# diag.net
KiCad netlist of a schematic drawn in EAGLE
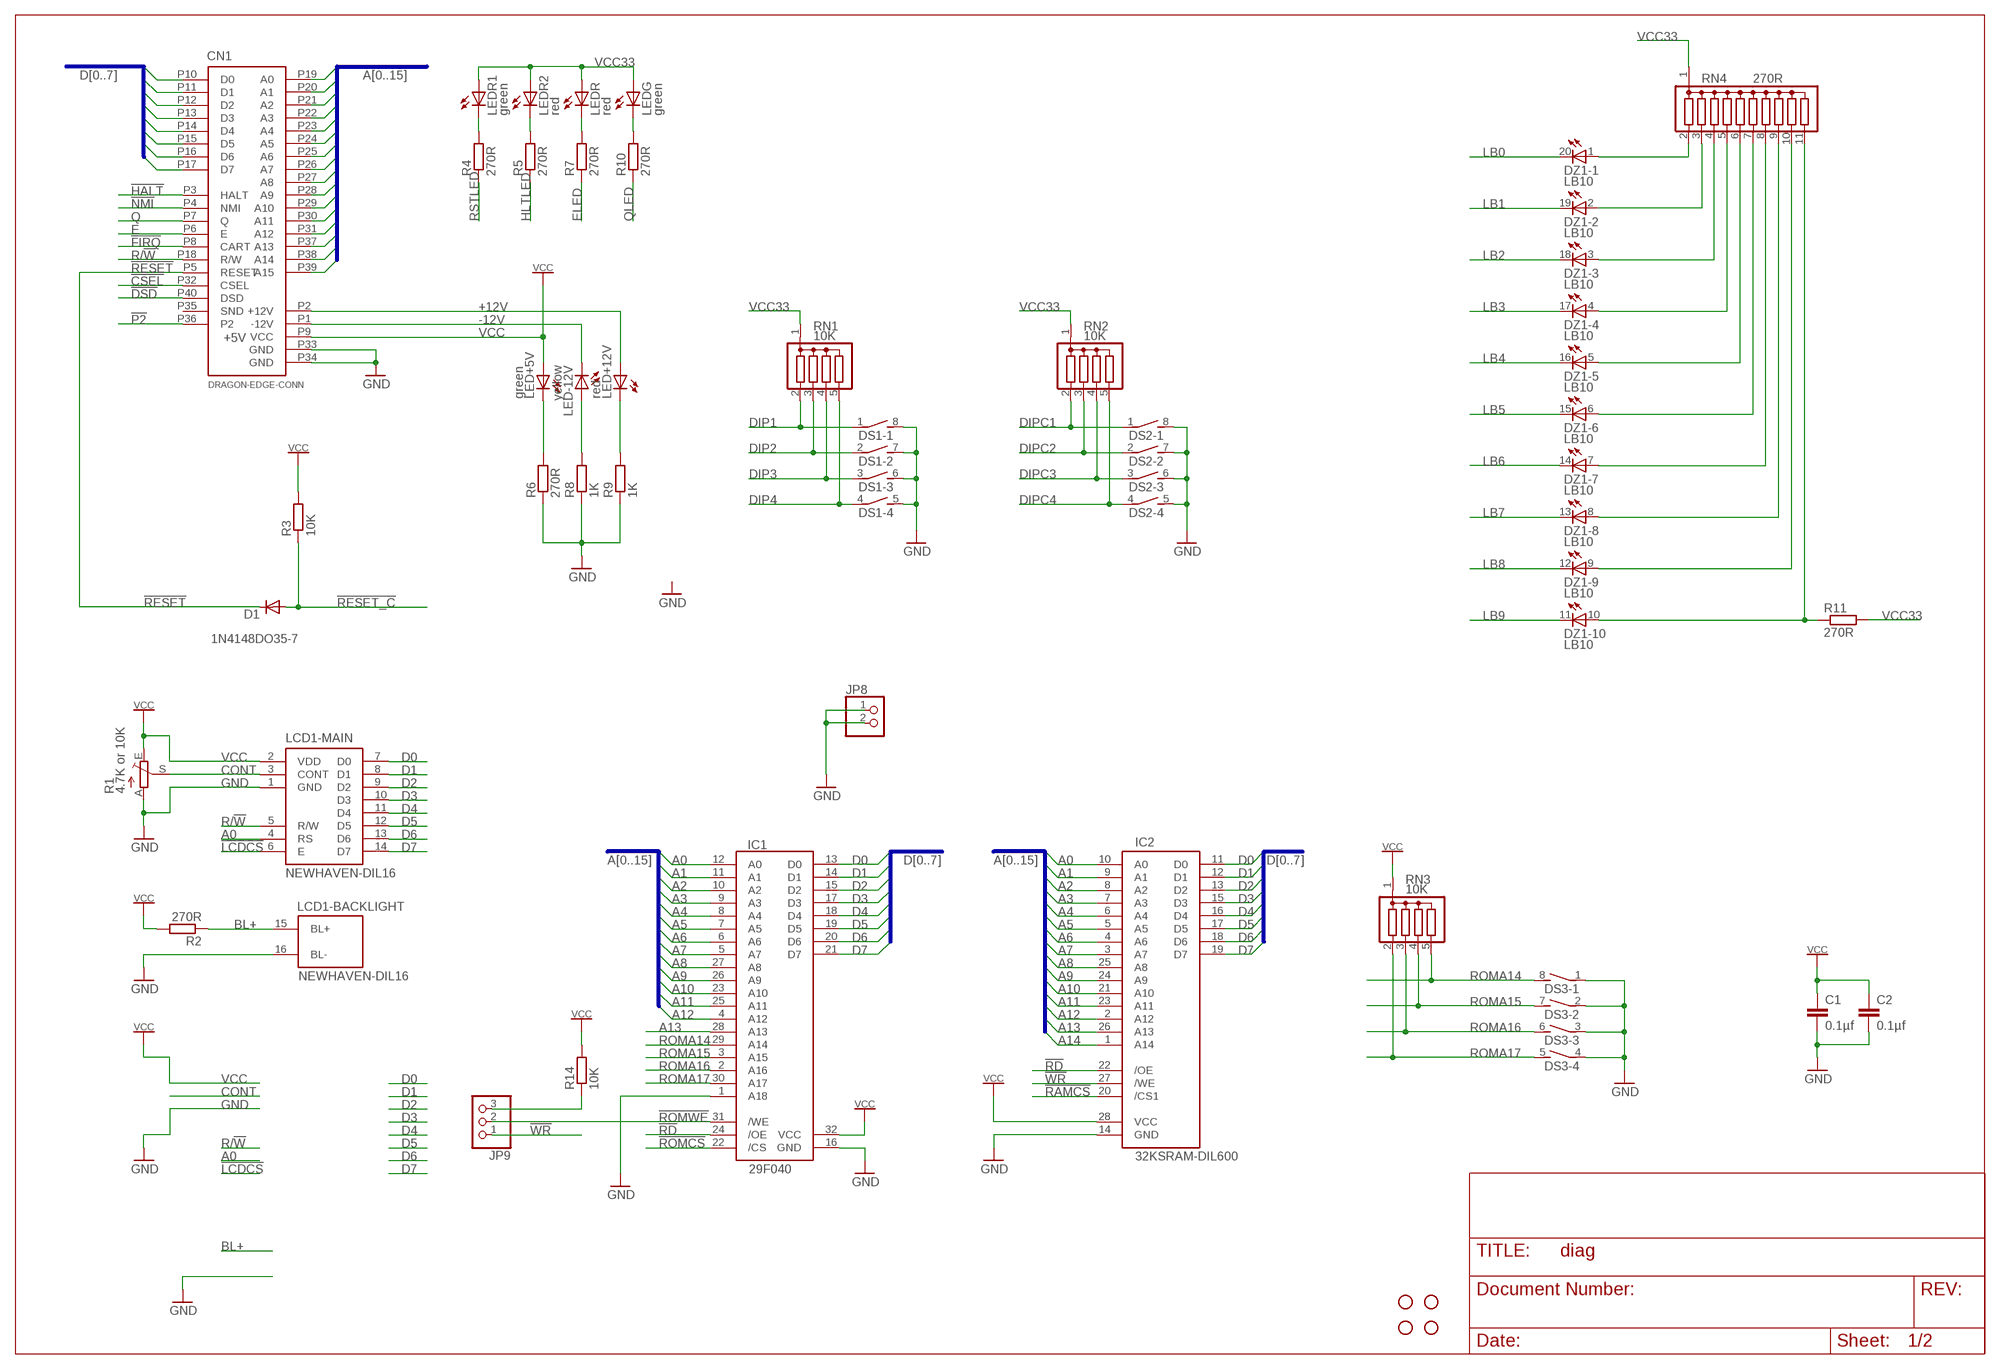
[diagram p0: schematic, sheet 1]
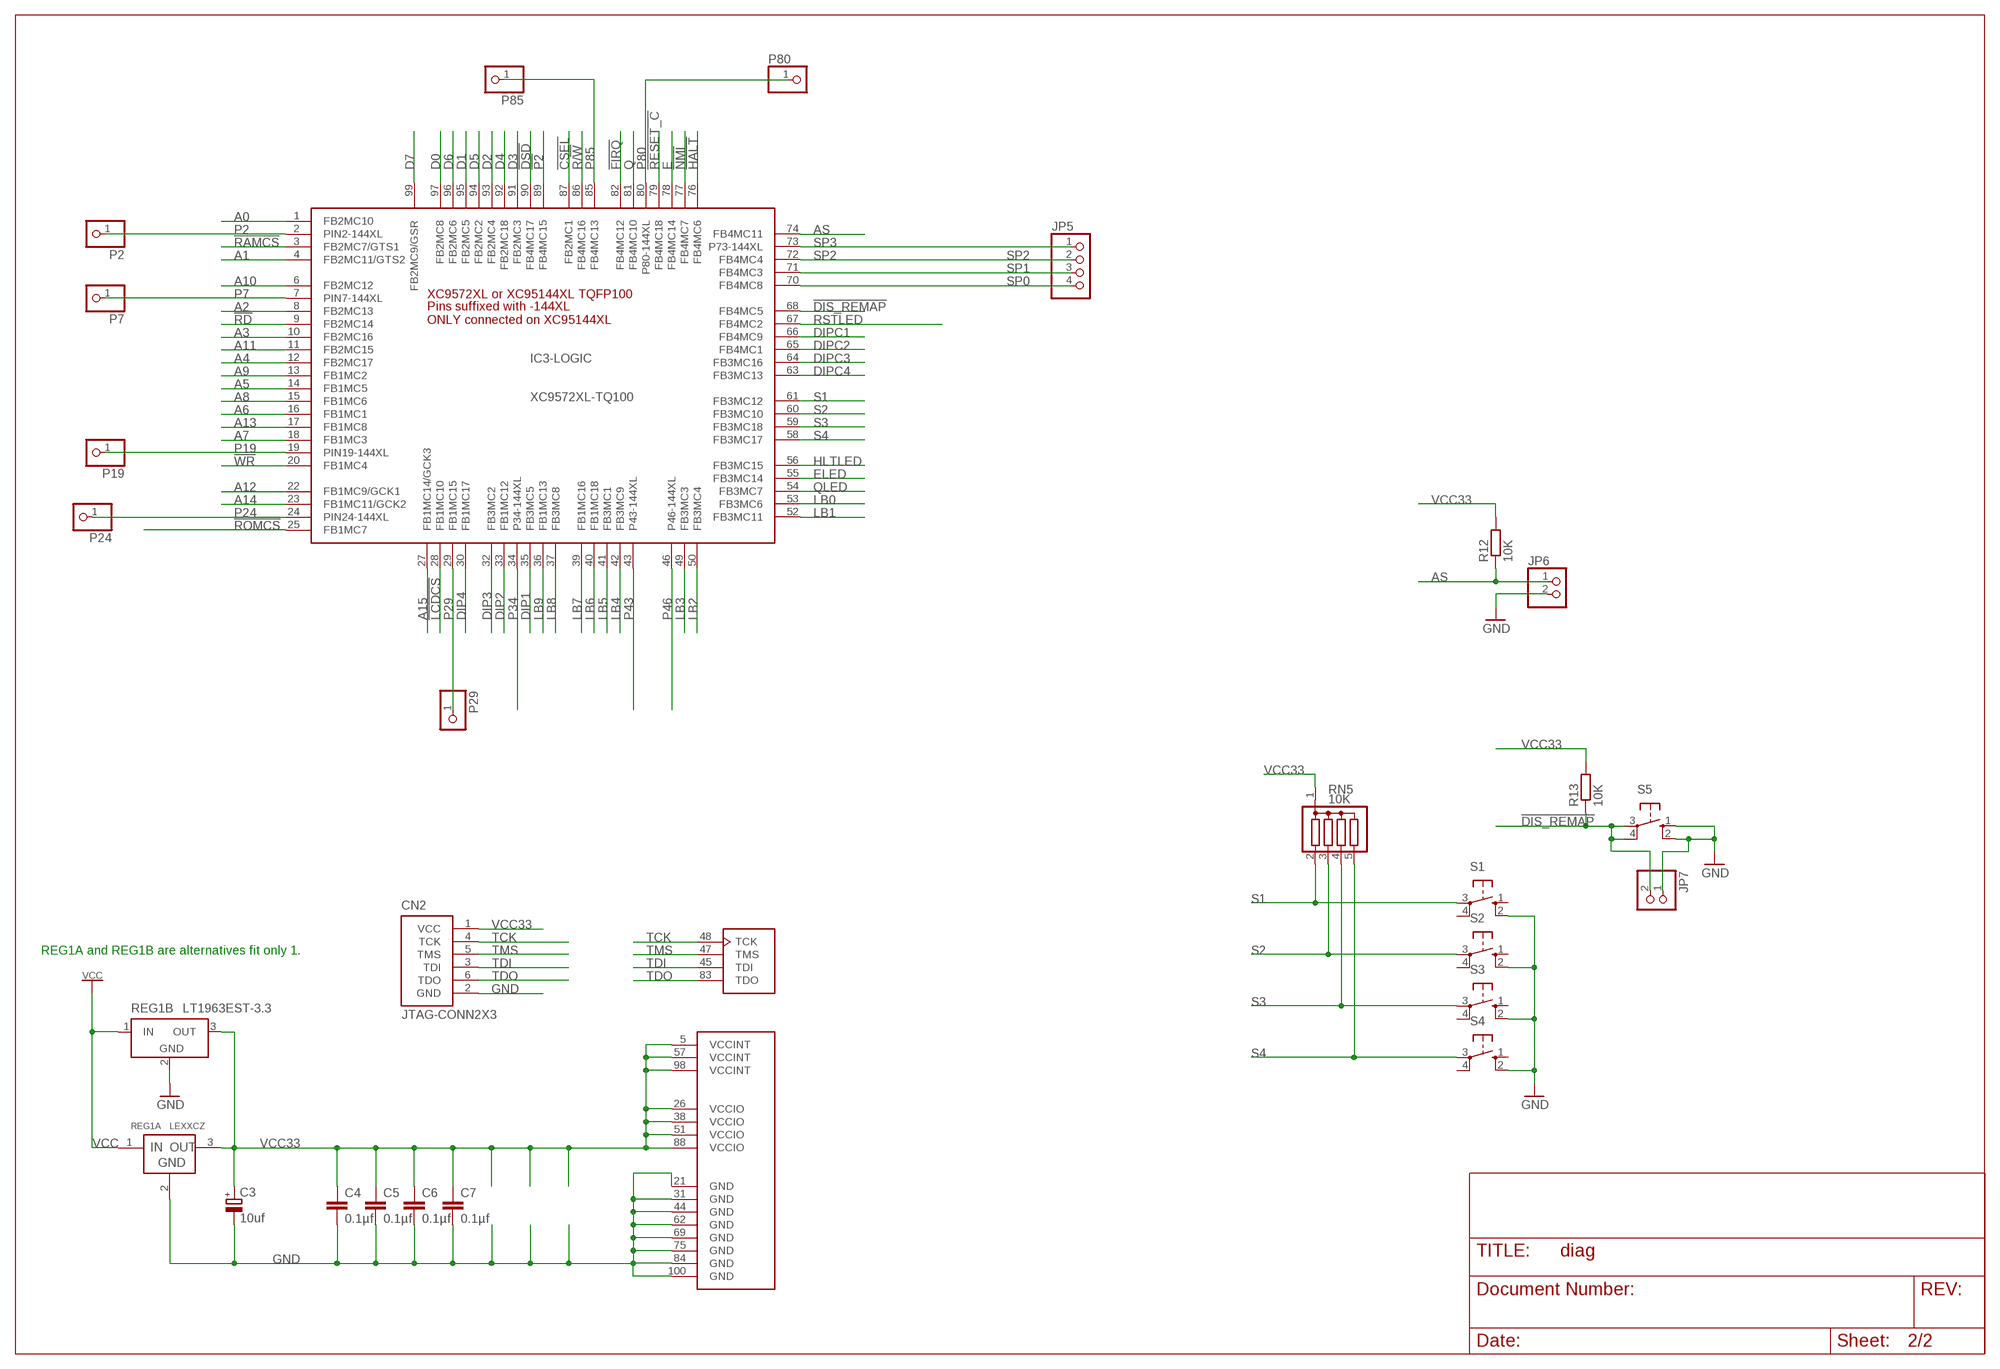
[diagram p1: schematic, sheet 2]

(export (version "E")
  (design (tool "Eeschema 10.0.6"))
  (components
    (comp (ref "C3")
      (value "10uf")
      (footprint "eagle-import:TT2D7")
      (libsource (lib "eagle-import") (part "CPOL-EUTT2D7"))
    )
    (comp (ref "C4")
      (value "0.1µf")
      (footprint "eagle-import:C025-025X050")
      (libsource (lib "eagle-import") (part "C-EU025-025X050"))
    )
    (comp (ref "C5")
      (value "0.1µf")
      (footprint "eagle-import:C025-025X050")
      (libsource (lib "eagle-import") (part "C-EU025-025X050"))
    )
    (comp (ref "C6")
      (value "0.1µf")
      (footprint "eagle-import:C025-025X050")
      (libsource (lib "eagle-import") (part "C-EU025-025X050"))
    )
    (comp (ref "C7")
      (value "0.1µf")
      (footprint "eagle-import:C025-025X050")
      (libsource (lib "eagle-import") (part "C-EU025-025X050"))
    )
    (comp (ref "CN2")
      (value "JTAG-CONN2X3")
      (footprint "eagle-import:2X3")
      (libsource (lib "eagle-import") (part "JTAG-CONN2X3"))
    )
    (comp (ref "IC3")
      (value "XC9572XL-TQ100")
      (footprint "eagle-import:TQ100")
      (libsource (lib "eagle-import") (part "XC9572XL-TQ100"))
    )
    (comp (ref "JP5")
      (value "PINHD-1X4")
      (footprint "eagle-import:1X04")
      (libsource (lib "eagle-import") (part "PINHD-1X4"))
    )
    (comp (ref "JP6")
      (value "PINHD-1X2")
      (footprint "eagle-import:1X02")
      (libsource (lib "eagle-import") (part "PINHD-1X2"))
    )
    (comp (ref "JP7")
      (value "PINHD-1X2")
      (footprint "eagle-import:1X02")
      (libsource (lib "eagle-import") (part "PINHD-1X2"))
    )
    (comp (ref "P2")
      (value "PINHD-1X1")
      (footprint "eagle-import:1X01")
      (libsource (lib "eagle-import") (part "PINHD-1X1"))
    )
    (comp (ref "P7")
      (value "PINHD-1X1")
      (footprint "eagle-import:1X01")
      (libsource (lib "eagle-import") (part "PINHD-1X1"))
    )
    (comp (ref "P19")
      (value "PINHD-1X1")
      (footprint "eagle-import:1X01")
      (libsource (lib "eagle-import") (part "PINHD-1X1"))
    )
    (comp (ref "P24")
      (value "PINHD-1X1")
      (footprint "eagle-import:1X01")
      (libsource (lib "eagle-import") (part "PINHD-1X1"))
    )
    (comp (ref "P29")
      (value "PINHD-1X1")
      (footprint "eagle-import:1X01")
      (libsource (lib "eagle-import") (part "PINHD-1X1"))
    )
    (comp (ref "P80")
      (value "PINHD-1X1")
      (footprint "eagle-import:1X01")
      (libsource (lib "eagle-import") (part "PINHD-1X1"))
    )
    (comp (ref "P85")
      (value "PINHD-1X1")
      (footprint "eagle-import:1X01")
      (libsource (lib "eagle-import") (part "PINHD-1X1"))
    )
    (comp (ref "R12")
      (value "10K")
      (footprint "eagle-import:0207_10")
      (libsource (lib "eagle-import") (part "R-EU_0207/10"))
    )
    (comp (ref "R13")
      (value "10K")
      (footprint "eagle-import:0207_10")
      (libsource (lib "eagle-import") (part "R-EU_0207/10"))
    )
    (comp (ref "REG1A")
      (value "LEXXCZ")
      (footprint "eagle-import:TO92-")
      (libsource (lib "eagle-import") (part "LEXXCZ"))
    )
    (comp (ref "REG1B")
      (value "LT1963EST-3.3")
      (footprint "eagle-import:SOT223")
      (libsource (lib "eagle-import") (part "LT1963EST-3.3"))
    )
    (comp (ref "RN5")
      (value "10K")
      (footprint "eagle-import:SIL5")
      (libsource (lib "eagle-import") (part "G04R"))
    )
    (comp (ref "S1")
      (value "10-XX")
      (footprint "eagle-import:B3F-10XX")
      (fields (field (name "MPN") "B3F-1000"))
      (libsource (lib "eagle-import") (part "10-XX"))
    )
    (comp (ref "S2")
      (value "10-XX")
      (footprint "eagle-import:B3F-10XX")
      (fields (field (name "MPN") "B3F-1000"))
      (libsource (lib "eagle-import") (part "10-XX"))
    )
    (comp (ref "S3")
      (value "10-XX")
      (footprint "eagle-import:B3F-10XX")
      (fields (field (name "MPN") "B3F-1000"))
      (libsource (lib "eagle-import") (part "10-XX"))
    )
    (comp (ref "S4")
      (value "10-XX")
      (footprint "eagle-import:B3F-10XX")
      (fields (field (name "MPN") "B3F-1000"))
      (libsource (lib "eagle-import") (part "10-XX"))
    )
    (comp (ref "S5")
      (value "10-XX")
      (footprint "eagle-import:B3F-10XX")
      (fields (field (name "MPN") "B3F-1000"))
      (libsource (lib "eagle-import") (part "10-XX"))
    )
    (comp (ref "C1")
      (value "0.1µf")
      (footprint "eagle-import:C025-025X050")
      (libsource (lib "eagle-import") (part "C-EU025-025X050"))
    )
    (comp (ref "C2")
      (value "0.1µf")
      (footprint "eagle-import:C025-025X050")
      (libsource (lib "eagle-import") (part "C-EU025-025X050"))
    )
    (comp (ref "CN1")
      (value "DRAGON-EDGE-CONN")
      (footprint "eagle-import:EDGE-40-01")
      (libsource (lib "eagle-import") (part "DRAGON-EDGE-CONN"))
    )
    (comp (ref "D1")
      (value "1N4148DO35-7")
      (footprint "eagle-import:DO35-7")
      (libsource (lib "eagle-import") (part "1N4148DO35-7"))
    )
    (comp (ref "DS1")
      (value "DIP04S")
      (footprint "eagle-import:DIP04S")
      (libsource (lib "eagle-import") (part "DIP04S"))
    )
    (comp (ref "DS2")
      (value "DIP04S")
      (footprint "eagle-import:DIP04S")
      (libsource (lib "eagle-import") (part "DIP04S"))
    )
    (comp (ref "DS3")
      (value "DIP04S")
      (footprint "eagle-import:DIP04S")
      (libsource (lib "eagle-import") (part "DIP04S"))
    )
    (comp (ref "DZ1")
      (value "LB10")
      (footprint "eagle-import:LB10")
      (libsource (lib "eagle-import") (part "LB10"))
    )
    (comp (ref "IC1")
      (value "29F040")
      (footprint "eagle-import:DIL32")
      (libsource (lib "eagle-import") (part "29F040"))
    )
    (comp (ref "IC2")
      (value "32KSRAM-DIL600")
      (footprint "eagle-import:DIL28-6")
      (libsource (lib "eagle-import") (part "32KSRAM-DIL600"))
    )
    (comp (ref "JP1")
      (value "STAND-OFF")
      (footprint "eagle-import:STAND-OFF")
      (libsource (lib "eagle-import") (part "STAND-OFF"))
    )
    (comp (ref "JP2")
      (value "STAND-OFF")
      (footprint "eagle-import:STAND-OFF")
      (libsource (lib "eagle-import") (part "STAND-OFF"))
    )
    (comp (ref "JP3")
      (value "STAND-OFF")
      (footprint "eagle-import:STAND-OFF")
      (libsource (lib "eagle-import") (part "STAND-OFF"))
    )
    (comp (ref "JP4")
      (value "STAND-OFF")
      (footprint "eagle-import:STAND-OFF")
      (libsource (lib "eagle-import") (part "STAND-OFF"))
    )
    (comp (ref "JP8")
      (value "PINHD-1X2")
      (footprint "eagle-import:1X02")
      (libsource (lib "eagle-import") (part "PINHD-1X2"))
    )
    (comp (ref "JP9")
      (value "PINHD-1X3")
      (footprint "eagle-import:1X03")
      (libsource (lib "eagle-import") (part "PINHD-1X3"))
    )
    (comp (ref "LCD1")
      (value "NEWHAVEN-DIL16")
      (footprint "eagle-import:2X08")
      (libsource (lib "eagle-import") (part "NEWHAVEN-DIL16"))
    )
    (comp (ref "LED+5V")
      (value "green")
      (footprint "eagle-import:LED3MM")
      (libsource (lib "eagle-import") (part "LED3MM"))
    )
    (comp (ref "LED+12V")
      (value "red")
      (footprint "eagle-import:LED3MM")
      (libsource (lib "eagle-import") (part "LED3MM"))
    )
    (comp (ref "LED-12V")
      (value "yellow")
      (footprint "eagle-import:LED3MM")
      (libsource (lib "eagle-import") (part "LED3MM"))
    )
    (comp (ref "LEDG")
      (value "green")
      (footprint "eagle-import:LED3MM")
      (libsource (lib "eagle-import") (part "LED3MM"))
    )
    (comp (ref "LEDR")
      (value "red")
      (footprint "eagle-import:LED3MM")
      (libsource (lib "eagle-import") (part "LED3MM"))
    )
    (comp (ref "LEDR1")
      (value "green")
      (footprint "eagle-import:LED3MM")
      (libsource (lib "eagle-import") (part "LED3MM"))
    )
    (comp (ref "LEDR2")
      (value "red")
      (footprint "eagle-import:LED3MM")
      (libsource (lib "eagle-import") (part "LED3MM"))
    )
    (comp (ref "R1")
      (value "4.7K or 10K")
      (footprint "eagle-import:CA9V")
      (libsource (lib "eagle-import") (part "TRIM_EU-CA9V"))
    )
    (comp (ref "R2")
      (value "270R")
      (footprint "eagle-import:0207_10")
      (libsource (lib "eagle-import") (part "R-EU_0207/10"))
    )
    (comp (ref "R3")
      (value "10K")
      (footprint "eagle-import:0204_7")
      (libsource (lib "eagle-import") (part "R-EU_0204/7"))
    )
    (comp (ref "R4")
      (value "270R")
      (footprint "eagle-import:0207_10")
      (libsource (lib "eagle-import") (part "R-EU_0207/10"))
    )
    (comp (ref "R5")
      (value "270R")
      (footprint "eagle-import:0207_10")
      (libsource (lib "eagle-import") (part "R-EU_0207/10"))
    )
    (comp (ref "R6")
      (value "270R")
      (footprint "eagle-import:0207_10")
      (libsource (lib "eagle-import") (part "R-EU_0207/10"))
    )
    (comp (ref "R7")
      (value "270R")
      (footprint "eagle-import:0207_10")
      (libsource (lib "eagle-import") (part "R-EU_0207/10"))
    )
    (comp (ref "R8")
      (value "1K")
      (footprint "eagle-import:0207_10")
      (libsource (lib "eagle-import") (part "R-EU_0207/10"))
    )
    (comp (ref "R9")
      (value "1K")
      (footprint "eagle-import:0207_10")
      (libsource (lib "eagle-import") (part "R-EU_0207/10"))
    )
    (comp (ref "R10")
      (value "270R")
      (footprint "eagle-import:0207_10")
      (libsource (lib "eagle-import") (part "R-EU_0207/10"))
    )
    (comp (ref "R11")
      (value "270R")
      (footprint "eagle-import:0207_10")
      (libsource (lib "eagle-import") (part "R-EU_0207/10"))
    )
    (comp (ref "R14")
      (value "10K")
      (footprint "eagle-import:0207_10")
      (libsource (lib "eagle-import") (part "R-EU_0207/10"))
    )
    (comp (ref "RN1")
      (value "10K")
      (footprint "eagle-import:SIL5")
      (libsource (lib "eagle-import") (part "G04R"))
    )
    (comp (ref "RN2")
      (value "10K")
      (footprint "eagle-import:SIL5")
      (libsource (lib "eagle-import") (part "G04R"))
    )
    (comp (ref "RN3")
      (value "10K")
      (footprint "eagle-import:SIL5")
      (libsource (lib "eagle-import") (part "G04R"))
    )
    (comp (ref "RN4")
      (value "270R")
      (footprint "eagle-import:SIL11")
      (libsource (lib "eagle-import") (part "G10R"))
    )
  )
  (nets
    (net (code "1") (name "+12V") (class "Default")
      (node (ref "CN1") (pin "P2") (pinfunction "+12V_P2") (pintype "passive"))
      (node (ref "LED+12V") (pin "A") (pinfunction "A_A") (pintype "passive"))
    )
    (net (code "2") (name "-12V") (class "Default")
      (node (ref "CN1") (pin "P1") (pinfunction "-12V_P1") (pintype "passive"))
      (node (ref "LED-12V") (pin "K") (pinfunction "C_K") (pintype "passive"))
    )
    (net (code "5") (name "A0") (class "Default")
      (node (ref "CN1") (pin "P19") (pinfunction "A0_P19") (pintype "passive"))
      (node (ref "IC1") (pin "12") (pinfunction "A0_12") (pintype "input"))
      (node (ref "IC2") (pin "10") (pinfunction "A0_10") (pintype "input"))
      (node (ref "IC3") (pin "1") (pinfunction "FB2MC10_1") (pintype "bidirectional"))
      (node (ref "LCD1") (pin "4") (pinfunction "RS_4") (pintype "bidirectional"))
    )
    (net (code "6") (name "A1") (class "Default")
      (node (ref "CN1") (pin "P20") (pinfunction "A1_P20") (pintype "passive"))
      (node (ref "IC1") (pin "11") (pinfunction "A1_11") (pintype "input"))
      (node (ref "IC2") (pin "9") (pinfunction "A1_9") (pintype "input"))
      (node (ref "IC3") (pin "4") (pinfunction "FB2MC11/GTS2_4") (pintype "bidirectional"))
    )
    (net (code "7") (name "A2") (class "Default")
      (node (ref "CN1") (pin "P21") (pinfunction "A2_P21") (pintype "passive"))
      (node (ref "IC1") (pin "10") (pinfunction "A2_10") (pintype "input"))
      (node (ref "IC2") (pin "8") (pinfunction "A2_8") (pintype "input"))
      (node (ref "IC3") (pin "8") (pinfunction "FB2MC13_8") (pintype "bidirectional"))
    )
    (net (code "8") (name "A3") (class "Default")
      (node (ref "CN1") (pin "P22") (pinfunction "A3_P22") (pintype "passive"))
      (node (ref "IC1") (pin "9") (pinfunction "A3_9") (pintype "input"))
      (node (ref "IC2") (pin "7") (pinfunction "A3_7") (pintype "input"))
      (node (ref "IC3") (pin "10") (pinfunction "FB2MC16_10") (pintype "bidirectional"))
    )
    (net (code "9") (name "A4") (class "Default")
      (node (ref "CN1") (pin "P23") (pinfunction "A4_P23") (pintype "passive"))
      (node (ref "IC1") (pin "8") (pinfunction "A4_8") (pintype "input"))
      (node (ref "IC2") (pin "6") (pinfunction "A4_6") (pintype "input"))
      (node (ref "IC3") (pin "12") (pinfunction "FB2MC17_12") (pintype "bidirectional"))
    )
    (net (code "10") (name "A5") (class "Default")
      (node (ref "CN1") (pin "P24") (pinfunction "A5_P24") (pintype "passive"))
      (node (ref "IC1") (pin "7") (pinfunction "A5_7") (pintype "input"))
      (node (ref "IC2") (pin "5") (pinfunction "A5_5") (pintype "input"))
      (node (ref "IC3") (pin "14") (pinfunction "FB1MC5_14") (pintype "bidirectional"))
    )
    (net (code "11") (name "A6") (class "Default")
      (node (ref "CN1") (pin "P25") (pinfunction "A6_P25") (pintype "passive"))
      (node (ref "IC1") (pin "6") (pinfunction "A6_6") (pintype "input"))
      (node (ref "IC2") (pin "4") (pinfunction "A6_4") (pintype "input"))
      (node (ref "IC3") (pin "16") (pinfunction "FB1MC1_16") (pintype "bidirectional"))
    )
    (net (code "12") (name "A7") (class "Default")
      (node (ref "CN1") (pin "P26") (pinfunction "A7_P26") (pintype "passive"))
      (node (ref "IC1") (pin "5") (pinfunction "A7_5") (pintype "input"))
      (node (ref "IC2") (pin "3") (pinfunction "A7_3") (pintype "input"))
      (node (ref "IC3") (pin "18") (pinfunction "FB1MC3_18") (pintype "bidirectional"))
    )
    (net (code "13") (name "A8") (class "Default")
      (node (ref "CN1") (pin "P27") (pinfunction "A8_P27") (pintype "passive"))
      (node (ref "IC1") (pin "27") (pinfunction "A8_27") (pintype "input"))
      (node (ref "IC2") (pin "25") (pinfunction "A8_25") (pintype "input"))
      (node (ref "IC3") (pin "15") (pinfunction "FB1MC6_15") (pintype "bidirectional"))
    )
    (net (code "14") (name "A9") (class "Default")
      (node (ref "CN1") (pin "P28") (pinfunction "A9_P28") (pintype "passive"))
      (node (ref "IC1") (pin "26") (pinfunction "A9_26") (pintype "input"))
      (node (ref "IC2") (pin "24") (pinfunction "A9_24") (pintype "input"))
      (node (ref "IC3") (pin "13") (pinfunction "FB1MC2_13") (pintype "bidirectional"))
    )
    (net (code "15") (name "A10") (class "Default")
      (node (ref "CN1") (pin "P29") (pinfunction "A10_P29") (pintype "passive"))
      (node (ref "IC1") (pin "23") (pinfunction "A10_23") (pintype "input"))
      (node (ref "IC2") (pin "21") (pinfunction "A10_21") (pintype "input"))
      (node (ref "IC3") (pin "6") (pinfunction "FB2MC12_6") (pintype "bidirectional"))
    )
    (net (code "16") (name "A11") (class "Default")
      (node (ref "CN1") (pin "P30") (pinfunction "A11_P30") (pintype "passive"))
      (node (ref "IC1") (pin "25") (pinfunction "A11_25") (pintype "input"))
      (node (ref "IC2") (pin "23") (pinfunction "A11_23") (pintype "input"))
      (node (ref "IC3") (pin "11") (pinfunction "FB2MC15_11") (pintype "bidirectional"))
    )
    (net (code "17") (name "A12") (class "Default")
      (node (ref "CN1") (pin "P31") (pinfunction "A12_P31") (pintype "passive"))
      (node (ref "IC1") (pin "4") (pinfunction "A12_4") (pintype "input"))
      (node (ref "IC2") (pin "2") (pinfunction "A12_2") (pintype "input"))
      (node (ref "IC3") (pin "22") (pinfunction "FB1MC9/GCK1_22") (pintype "bidirectional"))
    )
    (net (code "18") (name "A13") (class "Default")
      (node (ref "CN1") (pin "P37") (pinfunction "A13_P37") (pintype "passive"))
      (node (ref "IC1") (pin "28") (pinfunction "A13_28") (pintype "input"))
      (node (ref "IC2") (pin "26") (pinfunction "A13_26") (pintype "input"))
      (node (ref "IC3") (pin "17") (pinfunction "FB1MC8_17") (pintype "bidirectional"))
    )
    (net (code "19") (name "A14") (class "Default")
      (node (ref "CN1") (pin "P38") (pinfunction "A14_P38") (pintype "passive"))
      (node (ref "IC2") (pin "1") (pinfunction "A14_1") (pintype "input"))
      (node (ref "IC3") (pin "23") (pinfunction "FB1MC11/GCK2_23") (pintype "bidirectional"))
    )
    (net (code "20") (name "A15") (class "Default")
      (node (ref "CN1") (pin "P39") (pinfunction "A15_P39") (pintype "passive"))
      (node (ref "IC3") (pin "27") (pinfunction "FB1MC14/GCK3_27") (pintype "bidirectional"))
    )
    (net (code "21") (name "AS") (class "Default")
      (node (ref "IC3") (pin "74") (pinfunction "FB4MC11_74") (pintype "bidirectional"))
      (node (ref "JP6") (pin "1") (pinfunction "1_1") (pintype "passive"))
      (node (ref "R12") (pin "1") (pinfunction "1_1") (pintype "passive"))
    )
    (net (code "22") (name "BL+") (class "Default")
      (node (ref "LCD1") (pin "15") (pinfunction "BL+_15") (pintype "bidirectional"))
      (node (ref "R2") (pin "1") (pinfunction "1_1") (pintype "passive"))
    )
    (net (code "23") (name "CONT") (class "Default")
      (node (ref "LCD1") (pin "3") (pinfunction "CONT_3") (pintype "bidirectional"))
      (node (ref "R1") (pin "S") (pinfunction "S_S") (pintype "passive"))
    )
    (net (code "24") (name "D0") (class "Default")
      (node (ref "CN1") (pin "P10") (pinfunction "D0_P10") (pintype "passive"))
      (node (ref "IC1") (pin "13") (pinfunction "D0_13") (pintype "bidirectional"))
      (node (ref "IC2") (pin "11") (pinfunction "D0_11") (pintype "bidirectional"))
      (node (ref "IC3") (pin "97") (pinfunction "FB2MC8_97") (pintype "bidirectional"))
      (node (ref "LCD1") (pin "7") (pinfunction "D0_7") (pintype "bidirectional"))
    )
    (net (code "25") (name "D1") (class "Default")
      (node (ref "CN1") (pin "P11") (pinfunction "D1_P11") (pintype "passive"))
      (node (ref "IC1") (pin "14") (pinfunction "D1_14") (pintype "bidirectional"))
      (node (ref "IC2") (pin "12") (pinfunction "D1_12") (pintype "bidirectional"))
      (node (ref "IC3") (pin "95") (pinfunction "FB2MC5_95") (pintype "bidirectional"))
      (node (ref "LCD1") (pin "8") (pinfunction "D1_8") (pintype "bidirectional"))
    )
    (net (code "26") (name "D2") (class "Default")
      (node (ref "CN1") (pin "P12") (pinfunction "D2_P12") (pintype "passive"))
      (node (ref "IC1") (pin "15") (pinfunction "D2_15") (pintype "bidirectional"))
      (node (ref "IC2") (pin "13") (pinfunction "D2_13") (pintype "bidirectional"))
      (node (ref "IC3") (pin "93") (pinfunction "FB2MC4_93") (pintype "bidirectional"))
      (node (ref "LCD1") (pin "9") (pinfunction "D2_9") (pintype "bidirectional"))
    )
    (net (code "27") (name "D3") (class "Default")
      (node (ref "CN1") (pin "P13") (pinfunction "D3_P13") (pintype "passive"))
      (node (ref "IC1") (pin "17") (pinfunction "D3_17") (pintype "bidirectional"))
      (node (ref "IC2") (pin "15") (pinfunction "D3_15") (pintype "bidirectional"))
      (node (ref "IC3") (pin "91") (pinfunction "FB2MC3_91") (pintype "bidirectional"))
      (node (ref "LCD1") (pin "10") (pinfunction "D3_10") (pintype "bidirectional"))
    )
    (net (code "28") (name "D4") (class "Default")
      (node (ref "CN1") (pin "P14") (pinfunction "D4_P14") (pintype "passive"))
      (node (ref "IC1") (pin "18") (pinfunction "D4_18") (pintype "bidirectional"))
      (node (ref "IC2") (pin "16") (pinfunction "D4_16") (pintype "bidirectional"))
      (node (ref "IC3") (pin "92") (pinfunction "FB2MC18_92") (pintype "bidirectional"))
      (node (ref "LCD1") (pin "11") (pinfunction "D4_11") (pintype "bidirectional"))
    )
    (net (code "29") (name "D5") (class "Default")
      (node (ref "CN1") (pin "P15") (pinfunction "D5_P15") (pintype "passive"))
      (node (ref "IC1") (pin "19") (pinfunction "D5_19") (pintype "bidirectional"))
      (node (ref "IC2") (pin "17") (pinfunction "D5_17") (pintype "bidirectional"))
      (node (ref "IC3") (pin "94") (pinfunction "FB2MC2_94") (pintype "bidirectional"))
      (node (ref "LCD1") (pin "12") (pinfunction "D5_12") (pintype "bidirectional"))
    )
    (net (code "30") (name "D6") (class "Default")
      (node (ref "CN1") (pin "P16") (pinfunction "D6_P16") (pintype "passive"))
      (node (ref "IC1") (pin "20") (pinfunction "D6_20") (pintype "bidirectional"))
      (node (ref "IC2") (pin "18") (pinfunction "D6_18") (pintype "bidirectional"))
      (node (ref "IC3") (pin "96") (pinfunction "FB2MC6_96") (pintype "bidirectional"))
      (node (ref "LCD1") (pin "13") (pinfunction "D6_13") (pintype "bidirectional"))
    )
    (net (code "31") (name "D7") (class "Default")
      (node (ref "CN1") (pin "P17") (pinfunction "D7_P17") (pintype "passive"))
      (node (ref "IC1") (pin "21") (pinfunction "D7_21") (pintype "bidirectional"))
      (node (ref "IC2") (pin "19") (pinfunction "D7_19") (pintype "bidirectional"))
      (node (ref "IC3") (pin "99") (pinfunction "FB2MC9/GSR_99") (pintype "bidirectional"))
      (node (ref "LCD1") (pin "14") (pinfunction "D7_14") (pintype "bidirectional"))
    )
    (net (code "32") (name "DIP1") (class "Default")
      (node (ref "DS1") (pin "1") (pinfunction "1_1") (pintype "passive"))
      (node (ref "IC3") (pin "35") (pinfunction "FB3MC5_35") (pintype "bidirectional"))
      (node (ref "RN1") (pin "2") (pinfunction "2_2") (pintype "passive"))
    )
    (net (code "33") (name "DIP2") (class "Default")
      (node (ref "DS1") (pin "2") (pinfunction "1_2") (pintype "passive"))
      (node (ref "IC3") (pin "33") (pinfunction "FB1MC12_33") (pintype "bidirectional"))
      (node (ref "RN1") (pin "3") (pinfunction "3_3") (pintype "passive"))
    )
    (net (code "34") (name "DIP3") (class "Default")
      (node (ref "DS1") (pin "3") (pinfunction "1_3") (pintype "passive"))
      (node (ref "IC3") (pin "32") (pinfunction "FB3MC2_32") (pintype "bidirectional"))
      (node (ref "RN1") (pin "4") (pinfunction "4_4") (pintype "passive"))
    )
    (net (code "35") (name "DIP4") (class "Default")
      (node (ref "DS1") (pin "4") (pinfunction "1_4") (pintype "passive"))
      (node (ref "IC3") (pin "30") (pinfunction "FB1MC17_30") (pintype "bidirectional"))
      (node (ref "RN1") (pin "5") (pinfunction "5_5") (pintype "passive"))
    )
    (net (code "36") (name "DIPC1") (class "Default")
      (node (ref "DS2") (pin "1") (pinfunction "1_1") (pintype "passive"))
      (node (ref "IC3") (pin "66") (pinfunction "FB4MC9_66") (pintype "bidirectional"))
      (node (ref "RN2") (pin "2") (pinfunction "2_2") (pintype "passive"))
    )
    (net (code "37") (name "DIPC2") (class "Default")
      (node (ref "DS2") (pin "2") (pinfunction "1_2") (pintype "passive"))
      (node (ref "IC3") (pin "65") (pinfunction "FB4MC1_65") (pintype "bidirectional"))
      (node (ref "RN2") (pin "3") (pinfunction "3_3") (pintype "passive"))
    )
    (net (code "38") (name "DIPC3") (class "Default")
      (node (ref "DS2") (pin "3") (pinfunction "1_3") (pintype "passive"))
      (node (ref "IC3") (pin "64") (pinfunction "FB3MC16_64") (pintype "bidirectional"))
      (node (ref "RN2") (pin "4") (pinfunction "4_4") (pintype "passive"))
    )
    (net (code "39") (name "DIPC4") (class "Default")
      (node (ref "DS2") (pin "4") (pinfunction "1_4") (pintype "passive"))
      (node (ref "IC3") (pin "63") (pinfunction "FB3MC13_63") (pintype "bidirectional"))
      (node (ref "RN2") (pin "5") (pinfunction "5_5") (pintype "passive"))
    )
    (net (code "40") (name "E") (class "Default")
      (node (ref "CN1") (pin "P6") (pinfunction "E_P6") (pintype "passive"))
      (node (ref "IC3") (pin "78") (pinfunction "FB4MC14_78") (pintype "bidirectional"))
    )
    (net (code "41") (name "ELED") (class "Default")
      (node (ref "IC3") (pin "55") (pinfunction "FB3MC14_55") (pintype "bidirectional"))
      (node (ref "R7") (pin "1") (pinfunction "1_1") (pintype "passive"))
    )
    (net (code "42") (name "GND") (class "Default")
      (node (ref "C1") (pin "2") (pinfunction "2_2") (pintype "passive"))
      (node (ref "C2") (pin "2") (pinfunction "2_2") (pintype "passive"))
      (node (ref "C3") (pin "-") (pinfunction "-_-") (pintype "passive"))
      (node (ref "C4") (pin "2") (pinfunction "2_2") (pintype "passive"))
      (node (ref "C5") (pin "2") (pinfunction "2_2") (pintype "passive"))
      (node (ref "C6") (pin "2") (pinfunction "2_2") (pintype "passive"))
      (node (ref "C7") (pin "2") (pinfunction "2_2") (pintype "passive"))
      (node (ref "CN1") (pin "P33") (pinfunction "GND_P33") (pintype "passive"))
      (node (ref "CN1") (pin "P34") (pinfunction "GND_P34") (pintype "passive"))
      (node (ref "CN2") (pin "2") (pinfunction "GND_2") (pintype "bidirectional"))
      (node (ref "DS1") (pin "5") (pinfunction "2_5") (pintype "passive"))
      (node (ref "DS1") (pin "6") (pinfunction "2_6") (pintype "passive"))
      (node (ref "DS1") (pin "7") (pinfunction "2_7") (pintype "passive"))
      (node (ref "DS1") (pin "8") (pinfunction "2_8") (pintype "passive"))
      (node (ref "DS2") (pin "5") (pinfunction "2_5") (pintype "passive"))
      (node (ref "DS2") (pin "6") (pinfunction "2_6") (pintype "passive"))
      (node (ref "DS2") (pin "7") (pinfunction "2_7") (pintype "passive"))
      (node (ref "DS2") (pin "8") (pinfunction "2_8") (pintype "passive"))
      (node (ref "DS3") (pin "1") (pinfunction "1_1") (pintype "passive"))
      (node (ref "DS3") (pin "2") (pinfunction "1_2") (pintype "passive"))
      (node (ref "DS3") (pin "3") (pinfunction "1_3") (pintype "passive"))
      (node (ref "DS3") (pin "4") (pinfunction "1_4") (pintype "passive"))
      (node (ref "IC1") (pin "1") (pinfunction "A18_1") (pintype "input"))
      (node (ref "IC1") (pin "16") (pinfunction "GND_16") (pintype "power_in"))
      (node (ref "IC2") (pin "14") (pinfunction "GND_14") (pintype "power_in"))
      (node (ref "IC3") (pin "100") (pinfunction "GND_100") (pintype "power_in"))
      (node (ref "IC3") (pin "21") (pinfunction "GND_21") (pintype "power_in"))
      (node (ref "IC3") (pin "31") (pinfunction "GND_31") (pintype "power_in"))
      (node (ref "IC3") (pin "44") (pinfunction "GND_44") (pintype "power_in"))
      (node (ref "IC3") (pin "62") (pinfunction "GND_62") (pintype "power_in"))
      (node (ref "IC3") (pin "69") (pinfunction "GND_69") (pintype "power_in"))
      (node (ref "IC3") (pin "75") (pinfunction "GND_75") (pintype "power_in"))
      (node (ref "IC3") (pin "84") (pinfunction "GND_84") (pintype "power_in"))
      (node (ref "JP6") (pin "2") (pinfunction "2_2") (pintype "passive"))
      (node (ref "JP7") (pin "1") (pinfunction "1_1") (pintype "passive"))
      (node (ref "JP8") (pin "1") (pinfunction "1_1") (pintype "passive"))
      (node (ref "JP8") (pin "2") (pinfunction "2_2") (pintype "passive"))
      (node (ref "LCD1") (pin "1") (pinfunction "GND_1") (pintype "bidirectional"))
      (node (ref "LCD1") (pin "16") (pinfunction "BL-_16") (pintype "bidirectional"))
      (node (ref "R1") (pin "A") (pinfunction "A_A") (pintype "passive"))
      (node (ref "R6") (pin "1") (pinfunction "1_1") (pintype "passive"))
      (node (ref "R8") (pin "1") (pinfunction "1_1") (pintype "passive"))
      (node (ref "R9") (pin "1") (pinfunction "1_1") (pintype "passive"))
      (node (ref "REG1A") (pin "2") (pinfunction "GND_2") (pintype "power_in"))
      (node (ref "REG1B") (pin "2") (pinfunction "GND_2") (pintype "power_in"))
      (node (ref "S1") (pin "2") (pinfunction "S1_2") (pintype "passive"))
      (node (ref "S2") (pin "2") (pinfunction "S1_2") (pintype "passive"))
      (node (ref "S3") (pin "2") (pinfunction "S1_2") (pintype "passive"))
      (node (ref "S4") (pin "2") (pinfunction "S1_2") (pintype "passive"))
      (node (ref "S5") (pin "1") (pinfunction "S_1") (pintype "passive"))
      (node (ref "S5") (pin "2") (pinfunction "S1_2") (pintype "passive"))
    )
    (net (code "43") (name "HLTLED") (class "Default")
      (node (ref "IC3") (pin "56") (pinfunction "FB3MC15_56") (pintype "bidirectional"))
      (node (ref "R5") (pin "1") (pinfunction "1_1") (pintype "passive"))
    )
    (net (code "44") (name "LB0") (class "Default")
      (node (ref "DZ1") (pin "20") (pinfunction "C_20") (pintype "passive"))
      (node (ref "IC3") (pin "53") (pinfunction "FB3MC6_53") (pintype "bidirectional"))
    )
    (net (code "45") (name "LB1") (class "Default")
      (node (ref "DZ1") (pin "19") (pinfunction "C_19") (pintype "passive"))
      (node (ref "IC3") (pin "52") (pinfunction "FB3MC11_52") (pintype "bidirectional"))
    )
    (net (code "46") (name "LB2") (class "Default")
      (node (ref "DZ1") (pin "18") (pinfunction "C_18") (pintype "passive"))
      (node (ref "IC3") (pin "50") (pinfunction "FB3MC4_50") (pintype "bidirectional"))
    )
    (net (code "47") (name "LB3") (class "Default")
      (node (ref "DZ1") (pin "17") (pinfunction "C_17") (pintype "passive"))
      (node (ref "IC3") (pin "49") (pinfunction "FB3MC3_49") (pintype "bidirectional"))
    )
    (net (code "48") (name "LB4") (class "Default")
      (node (ref "DZ1") (pin "16") (pinfunction "C_16") (pintype "passive"))
      (node (ref "IC3") (pin "42") (pinfunction "FB3MC9_42") (pintype "bidirectional"))
    )
    (net (code "49") (name "LB5") (class "Default")
      (node (ref "DZ1") (pin "15") (pinfunction "C_15") (pintype "passive"))
      (node (ref "IC3") (pin "41") (pinfunction "FB3MC1_41") (pintype "bidirectional"))
    )
    (net (code "50") (name "LB6") (class "Default")
      (node (ref "DZ1") (pin "14") (pinfunction "C_14") (pintype "passive"))
      (node (ref "IC3") (pin "40") (pinfunction "FB1MC18_40") (pintype "bidirectional"))
    )
    (net (code "51") (name "LB7") (class "Default")
      (node (ref "DZ1") (pin "13") (pinfunction "C_13") (pintype "passive"))
      (node (ref "IC3") (pin "39") (pinfunction "FB1MC16_39") (pintype "bidirectional"))
    )
    (net (code "52") (name "LB8") (class "Default")
      (node (ref "DZ1") (pin "12") (pinfunction "C_12") (pintype "passive"))
      (node (ref "IC3") (pin "37") (pinfunction "FB3MC8_37") (pintype "bidirectional"))
    )
    (net (code "53") (name "LB9") (class "Default")
      (node (ref "DZ1") (pin "11") (pinfunction "C_11") (pintype "passive"))
      (node (ref "IC3") (pin "36") (pinfunction "FB1MC13_36") (pintype "bidirectional"))
    )
    (net (code "54") (name "Net-(DZ1A-A)") (class "Default")
      (node (ref "DZ1") (pin "1") (pinfunction "A_1") (pintype "passive"))
      (node (ref "RN4") (pin "2") (pinfunction "2_2") (pintype "passive"))
    )
    (net (code "55") (name "Net-(DZ1B-A)") (class "Default")
      (node (ref "DZ1") (pin "10") (pinfunction "A_10") (pintype "passive"))
      (node (ref "R11") (pin "1") (pinfunction "1_1") (pintype "passive"))
      (node (ref "RN4") (pin "11") (pinfunction "11_11") (pintype "passive"))
    )
    (net (code "56") (name "Net-(DZ1C-A)") (class "Default")
      (node (ref "DZ1") (pin "2") (pinfunction "A_2") (pintype "passive"))
      (node (ref "RN4") (pin "3") (pinfunction "3_3") (pintype "passive"))
    )
    (net (code "57") (name "Net-(DZ1D-A)") (class "Default")
      (node (ref "DZ1") (pin "3") (pinfunction "A_3") (pintype "passive"))
      (node (ref "RN4") (pin "4") (pinfunction "4_4") (pintype "passive"))
    )
    (net (code "58") (name "Net-(DZ1E-A)") (class "Default")
      (node (ref "DZ1") (pin "4") (pinfunction "A_4") (pintype "passive"))
      (node (ref "RN4") (pin "5") (pinfunction "5_5") (pintype "passive"))
    )
    (net (code "59") (name "Net-(DZ1F-A)") (class "Default")
      (node (ref "DZ1") (pin "5") (pinfunction "A_5") (pintype "passive"))
      (node (ref "RN4") (pin "6") (pinfunction "6_6") (pintype "passive"))
    )
    (net (code "60") (name "Net-(DZ1G-A)") (class "Default")
      (node (ref "DZ1") (pin "6") (pinfunction "A_6") (pintype "passive"))
      (node (ref "RN4") (pin "7") (pinfunction "7_7") (pintype "passive"))
    )
    (net (code "61") (name "Net-(DZ1H-A)") (class "Default")
      (node (ref "DZ1") (pin "7") (pinfunction "A_7") (pintype "passive"))
      (node (ref "RN4") (pin "8") (pinfunction "8_8") (pintype "passive"))
    )
    (net (code "62") (name "Net-(DZ1I-A)") (class "Default")
      (node (ref "DZ1") (pin "8") (pinfunction "A_8") (pintype "passive"))
      (node (ref "RN4") (pin "9") (pinfunction "9_9") (pintype "passive"))
    )
    (net (code "63") (name "Net-(DZ1J-A)") (class "Default")
      (node (ref "DZ1") (pin "9") (pinfunction "A_9") (pintype "passive"))
      (node (ref "RN4") (pin "10") (pinfunction "10_10") (pintype "passive"))
    )
    (net (code "64") (name "Net-(JP9-Pad3)") (class "Default")
      (node (ref "JP9") (pin "3") (pinfunction "3_3") (pintype "passive"))
      (node (ref "R14") (pin "1") (pinfunction "1_1") (pintype "passive"))
    )
    (net (code "65") (name "Net-(LED+5V-C)") (class "Default")
      (node (ref "LED+5V") (pin "K") (pinfunction "C_K") (pintype "passive"))
      (node (ref "R6") (pin "2") (pinfunction "2_2") (pintype "passive"))
    )
    (net (code "66") (name "Net-(LED+12V-C)") (class "Default")
      (node (ref "LED+12V") (pin "K") (pinfunction "C_K") (pintype "passive"))
      (node (ref "R9") (pin "2") (pinfunction "2_2") (pintype "passive"))
    )
    (net (code "67") (name "Net-(LED-12V-PadA)") (class "Default")
      (node (ref "LED-12V") (pin "A") (pinfunction "A_A") (pintype "passive"))
      (node (ref "R8") (pin "2") (pinfunction "2_2") (pintype "passive"))
    )
    (net (code "68") (name "Net-(LEDG-C)") (class "Default")
      (node (ref "LEDG") (pin "K") (pinfunction "C_K") (pintype "passive"))
      (node (ref "R10") (pin "2") (pinfunction "2_2") (pintype "passive"))
    )
    (net (code "69") (name "Net-(LEDR-C)") (class "Default")
      (node (ref "LEDR") (pin "K") (pinfunction "C_K") (pintype "passive"))
      (node (ref "R7") (pin "2") (pinfunction "2_2") (pintype "passive"))
    )
    (net (code "70") (name "Net-(LEDR1-C)") (class "Default")
      (node (ref "LEDR1") (pin "K") (pinfunction "C_K") (pintype "passive"))
      (node (ref "R4") (pin "2") (pinfunction "2_2") (pintype "passive"))
    )
    (net (code "71") (name "Net-(LEDR2-C)") (class "Default")
      (node (ref "LEDR2") (pin "K") (pinfunction "C_K") (pintype "passive"))
      (node (ref "R5") (pin "2") (pinfunction "2_2") (pintype "passive"))
    )
    (net (code "72") (name "P2") (class "Default")
      (node (ref "IC3") (pin "2") (pinfunction "PIN2-144XL_2") (pintype "bidirectional"))
      (node (ref "P2") (pin "1") (pinfunction "1_1") (pintype "passive"))
    )
    (net (code "73") (name "P7") (class "Default")
      (node (ref "IC3") (pin "7") (pinfunction "PIN7-144XL_7") (pintype "bidirectional"))
      (node (ref "P7") (pin "1") (pinfunction "1_1") (pintype "passive"))
    )
    (net (code "74") (name "P19") (class "Default")
      (node (ref "IC3") (pin "19") (pinfunction "PIN19-144XL_19") (pintype "bidirectional"))
      (node (ref "P19") (pin "1") (pinfunction "1_1") (pintype "passive"))
    )
    (net (code "75") (name "P24") (class "Default")
      (node (ref "IC3") (pin "24") (pinfunction "PIN24-144XL_24") (pintype "bidirectional"))
      (node (ref "P24") (pin "1") (pinfunction "1_1") (pintype "passive"))
    )
    (net (code "76") (name "P29") (class "Default")
      (node (ref "IC3") (pin "29") (pinfunction "FB1MC15_29") (pintype "bidirectional"))
      (node (ref "P29") (pin "1") (pinfunction "1_1") (pintype "passive"))
    )
    (net (code "77") (name "P34") (class "Default")
      (node (ref "IC3") (pin "34") (pinfunction "P34-144XL_34") (pintype "bidirectional"))
    )
    (net (code "78") (name "P43") (class "Default")
      (node (ref "IC3") (pin "43") (pinfunction "P43-144XL_43") (pintype "bidirectional"))
    )
    (net (code "79") (name "P46") (class "Default")
      (node (ref "IC3") (pin "46") (pinfunction "P46-144XL_46") (pintype "bidirectional"))
    )
    (net (code "80") (name "P80") (class "Default")
      (node (ref "IC3") (pin "80") (pinfunction "P80-144XL_80") (pintype "bidirectional"))
      (node (ref "P80") (pin "1") (pinfunction "1_1") (pintype "passive"))
    )
    (net (code "81") (name "P85") (class "Default")
      (node (ref "IC3") (pin "85") (pinfunction "FB4MC13_85") (pintype "bidirectional"))
      (node (ref "P85") (pin "1") (pinfunction "1_1") (pintype "passive"))
    )
    (net (code "82") (name "Q") (class "Default")
      (node (ref "CN1") (pin "P7") (pinfunction "Q_P7") (pintype "passive"))
      (node (ref "IC3") (pin "81") (pinfunction "FB4MC10_81") (pintype "bidirectional"))
    )
    (net (code "83") (name "QLED") (class "Default")
      (node (ref "IC3") (pin "54") (pinfunction "FB3MC7_54") (pintype "bidirectional"))
      (node (ref "R10") (pin "1") (pinfunction "1_1") (pintype "passive"))
    )
    (net (code "84") (name "ROMA14") (class "Default")
      (node (ref "DS3") (pin "8") (pinfunction "2_8") (pintype "passive"))
      (node (ref "IC1") (pin "29") (pinfunction "A14_29") (pintype "input"))
      (node (ref "RN3") (pin "5") (pinfunction "5_5") (pintype "passive"))
    )
    (net (code "85") (name "ROMA15") (class "Default")
      (node (ref "DS3") (pin "7") (pinfunction "2_7") (pintype "passive"))
      (node (ref "IC1") (pin "3") (pinfunction "A15_3") (pintype "input"))
      (node (ref "RN3") (pin "4") (pinfunction "4_4") (pintype "passive"))
    )
    (net (code "86") (name "ROMA16") (class "Default")
      (node (ref "DS3") (pin "6") (pinfunction "2_6") (pintype "passive"))
      (node (ref "IC1") (pin "2") (pinfunction "A16_2") (pintype "input"))
      (node (ref "RN3") (pin "3") (pinfunction "3_3") (pintype "passive"))
    )
    (net (code "87") (name "ROMA17") (class "Default")
      (node (ref "DS3") (pin "5") (pinfunction "2_5") (pintype "passive"))
      (node (ref "IC1") (pin "30") (pinfunction "A17_30") (pintype "input"))
      (node (ref "RN3") (pin "2") (pinfunction "2_2") (pintype "passive"))
    )
    (net (code "88") (name "RSTLED") (class "Default")
      (node (ref "IC3") (pin "67") (pinfunction "FB4MC2_67") (pintype "bidirectional"))
      (node (ref "R4") (pin "1") (pinfunction "1_1") (pintype "passive"))
    )
    (net (code "89") (name "R{slash}~{W}") (class "Default")
      (node (ref "CN1") (pin "P18") (pinfunction "R/W_P18") (pintype "passive"))
      (node (ref "IC3") (pin "86") (pinfunction "FB4MC16_86") (pintype "bidirectional"))
      (node (ref "LCD1") (pin "5") (pinfunction "R/W_5") (pintype "bidirectional"))
    )
    (net (code "90") (name "S1") (class "Default")
      (node (ref "IC3") (pin "61") (pinfunction "FB3MC12_61") (pintype "bidirectional"))
      (node (ref "RN5") (pin "2") (pinfunction "2_2") (pintype "passive"))
      (node (ref "S1") (pin "3") (pinfunction "P_3") (pintype "passive"))
    )
    (net (code "91") (name "S2") (class "Default")
      (node (ref "IC3") (pin "60") (pinfunction "FB3MC10_60") (pintype "bidirectional"))
      (node (ref "RN5") (pin "3") (pinfunction "3_3") (pintype "passive"))
      (node (ref "S2") (pin "3") (pinfunction "P_3") (pintype "passive"))
    )
    (net (code "92") (name "S3") (class "Default")
      (node (ref "IC3") (pin "59") (pinfunction "FB3MC18_59") (pintype "bidirectional"))
      (node (ref "RN5") (pin "4") (pinfunction "4_4") (pintype "passive"))
      (node (ref "S3") (pin "3") (pinfunction "P_3") (pintype "passive"))
    )
    (net (code "93") (name "S4") (class "Default")
      (node (ref "IC3") (pin "58") (pinfunction "FB3MC17_58") (pintype "bidirectional"))
      (node (ref "RN5") (pin "5") (pinfunction "5_5") (pintype "passive"))
      (node (ref "S4") (pin "3") (pinfunction "P_3") (pintype "passive"))
    )
    (net (code "94") (name "SP0") (class "Default")
      (node (ref "IC3") (pin "70") (pinfunction "FB4MC8_70") (pintype "bidirectional"))
      (node (ref "JP5") (pin "4") (pinfunction "4_4") (pintype "passive"))
    )
    (net (code "95") (name "SP1") (class "Default")
      (node (ref "IC3") (pin "71") (pinfunction "FB4MC3_71") (pintype "bidirectional"))
      (node (ref "JP5") (pin "3") (pinfunction "3_3") (pintype "passive"))
    )
    (net (code "96") (name "SP2") (class "Default")
      (node (ref "IC3") (pin "72") (pinfunction "FB4MC4_72") (pintype "bidirectional"))
      (node (ref "JP5") (pin "2") (pinfunction "2_2") (pintype "passive"))
    )
    (net (code "97") (name "SP3") (class "Default")
      (node (ref "IC3") (pin "73") (pinfunction "P73-144XL_73") (pintype "bidirectional"))
      (node (ref "JP5") (pin "1") (pinfunction "1_1") (pintype "passive"))
    )
    (net (code "98") (name "TCK") (class "Default")
      (node (ref "CN2") (pin "4") (pinfunction "TCK_4") (pintype "bidirectional"))
      (node (ref "IC3") (pin "48") (pinfunction "TCK_48") (pintype "input"))
    )
    (net (code "99") (name "TDI") (class "Default")
      (node (ref "CN2") (pin "3") (pinfunction "TDI_3") (pintype "bidirectional"))
      (node (ref "IC3") (pin "45") (pinfunction "TDI_45") (pintype "input"))
    )
    (net (code "100") (name "TDO") (class "Default")
      (node (ref "CN2") (pin "6") (pinfunction "TDO_6") (pintype "bidirectional"))
      (node (ref "IC3") (pin "83") (pinfunction "TDO_83") (pintype "output"))
    )
    (net (code "101") (name "TMS") (class "Default")
      (node (ref "CN2") (pin "5") (pinfunction "TMS_5") (pintype "bidirectional"))
      (node (ref "IC3") (pin "47") (pinfunction "TMS_47") (pintype "input"))
    )
    (net (code "102") (name "VCC") (class "Default")
      (node (ref "C1") (pin "1") (pinfunction "1_1") (pintype "passive"))
      (node (ref "C2") (pin "1") (pinfunction "1_1") (pintype "passive"))
      (node (ref "CN1") (pin "P9") (pinfunction "VCC_P9") (pintype "passive"))
      (node (ref "IC1") (pin "32") (pinfunction "VCC_32") (pintype "power_in"))
      (node (ref "IC2") (pin "28") (pinfunction "VCC_28") (pintype "power_in"))
      (node (ref "LCD1") (pin "2") (pinfunction "VDD_2") (pintype "bidirectional"))
      (node (ref "LED+5V") (pin "A") (pinfunction "A_A") (pintype "passive"))
      (node (ref "R1") (pin "E") (pinfunction "E_E") (pintype "passive"))
      (node (ref "R14") (pin "2") (pinfunction "2_2") (pintype "passive"))
      (node (ref "R2") (pin "2") (pinfunction "2_2") (pintype "passive"))
      (node (ref "R3") (pin "2") (pinfunction "2_2") (pintype "passive"))
      (node (ref "REG1A") (pin "1") (pinfunction "IN_1") (pintype "power_in"))
      (node (ref "REG1B") (pin "1") (pinfunction "IN_1") (pintype "input"))
      (node (ref "RN3") (pin "1") (pinfunction "1_1") (pintype "passive"))
    )
    (net (code "103") (name "VCC33") (class "Default")
      (node (ref "C3") (pin "+") (pinfunction "+_+") (pintype "passive"))
      (node (ref "C4") (pin "1") (pinfunction "1_1") (pintype "passive"))
      (node (ref "C5") (pin "1") (pinfunction "1_1") (pintype "passive"))
      (node (ref "C6") (pin "1") (pinfunction "1_1") (pintype "passive"))
      (node (ref "C7") (pin "1") (pinfunction "1_1") (pintype "passive"))
      (node (ref "CN2") (pin "1") (pinfunction "VCC_1") (pintype "bidirectional"))
      (node (ref "IC3") (pin "26") (pinfunction "VCCIO_26") (pintype "power_in"))
      (node (ref "IC3") (pin "38") (pinfunction "VCCIO_38") (pintype "power_in"))
      (node (ref "IC3") (pin "5") (pinfunction "VCCINT_5") (pintype "power_in"))
      (node (ref "IC3") (pin "51") (pinfunction "VCCIO_51") (pintype "power_in"))
      (node (ref "IC3") (pin "57") (pinfunction "VCCINT_57") (pintype "power_in"))
      (node (ref "IC3") (pin "88") (pinfunction "VCCIO_88") (pintype "power_in"))
      (node (ref "IC3") (pin "98") (pinfunction "VCCINT_98") (pintype "power_in"))
      (node (ref "LEDG") (pin "A") (pinfunction "A_A") (pintype "passive"))
      (node (ref "LEDR") (pin "A") (pinfunction "A_A") (pintype "passive"))
      (node (ref "LEDR1") (pin "A") (pinfunction "A_A") (pintype "passive"))
      (node (ref "LEDR2") (pin "A") (pinfunction "A_A") (pintype "passive"))
      (node (ref "R11") (pin "2") (pinfunction "2_2") (pintype "passive"))
      (node (ref "R12") (pin "2") (pinfunction "2_2") (pintype "passive"))
      (node (ref "R13") (pin "2") (pinfunction "2_2") (pintype "passive"))
      (node (ref "REG1A") (pin "3") (pinfunction "OUT_3") (pintype "power_in"))
      (node (ref "REG1B") (pin "3") (pinfunction "OUT_3") (pintype "output"))
      (node (ref "RN1") (pin "1") (pinfunction "1_1") (pintype "passive"))
      (node (ref "RN2") (pin "1") (pinfunction "1_1") (pintype "passive"))
      (node (ref "RN4") (pin "1") (pinfunction "1_1") (pintype "passive"))
      (node (ref "RN5") (pin "1") (pinfunction "1_1") (pintype "passive"))
    )
    (net (code "104") (name "unconnected-(CN1-SND-PadP35)") (class "Default")
      (node (ref "CN1") (pin "P35") (pinfunction "SND_P35") (pintype "passive"))
    )
    (net (code "105") (name "unconnected-(S1-P1-Pad4)") (class "Default")
      (node (ref "S1") (pin "4") (pinfunction "P1_4") (pintype "passive"))
    )
    (net (code "106") (name "unconnected-(S1-S-Pad1)") (class "Default")
      (node (ref "S1") (pin "1") (pinfunction "S_1") (pintype "passive"))
    )
    (net (code "107") (name "unconnected-(S2-P1-Pad4)") (class "Default")
      (node (ref "S2") (pin "4") (pinfunction "P1_4") (pintype "passive"))
    )
    (net (code "108") (name "unconnected-(S2-S-Pad1)") (class "Default")
      (node (ref "S2") (pin "1") (pinfunction "S_1") (pintype "passive"))
    )
    (net (code "109") (name "unconnected-(S3-P1-Pad4)") (class "Default")
      (node (ref "S3") (pin "4") (pinfunction "P1_4") (pintype "passive"))
    )
    (net (code "110") (name "unconnected-(S3-S-Pad1)") (class "Default")
      (node (ref "S3") (pin "1") (pinfunction "S_1") (pintype "passive"))
    )
    (net (code "111") (name "unconnected-(S4-P1-Pad4)") (class "Default")
      (node (ref "S4") (pin "4") (pinfunction "P1_4") (pintype "passive"))
    )
    (net (code "112") (name "unconnected-(S4-S-Pad1)") (class "Default")
      (node (ref "S4") (pin "1") (pinfunction "S_1") (pintype "passive"))
    )
    (net (code "113") (name "~{CSEL}") (class "Default")
      (node (ref "CN1") (pin "P32") (pinfunction "CSEL_P32") (pintype "passive"))
      (node (ref "IC3") (pin "87") (pinfunction "FB2MC1_87") (pintype "bidirectional"))
    )
    (net (code "114") (name "~{DIS_REMAP}") (class "Default")
      (node (ref "IC3") (pin "68") (pinfunction "FB4MC5_68") (pintype "bidirectional"))
      (node (ref "JP7") (pin "2") (pinfunction "2_2") (pintype "passive"))
      (node (ref "R13") (pin "1") (pinfunction "1_1") (pintype "passive"))
      (node (ref "S5") (pin "3") (pinfunction "P_3") (pintype "passive"))
      (node (ref "S5") (pin "4") (pinfunction "P1_4") (pintype "passive"))
    )
    (net (code "115") (name "~{DSD}") (class "Default")
      (node (ref "CN1") (pin "P40") (pinfunction "DSD_P40") (pintype "passive"))
      (node (ref "IC3") (pin "90") (pinfunction "FB4MC17_90") (pintype "bidirectional"))
    )
    (net (code "116") (name "~{FIRQ}") (class "Default")
      (node (ref "CN1") (pin "P8") (pinfunction "CART_P8") (pintype "passive"))
      (node (ref "IC3") (pin "82") (pinfunction "FB4MC12_82") (pintype "bidirectional"))
    )
    (net (code "117") (name "~{HALT}") (class "Default")
      (node (ref "CN1") (pin "P3") (pinfunction "HALT_P3") (pintype "passive"))
      (node (ref "IC3") (pin "76") (pinfunction "FB4MC6_76") (pintype "bidirectional"))
    )
    (net (code "118") (name "~{LCDCS}") (class "Default")
      (node (ref "IC3") (pin "28") (pinfunction "FB1MC10_28") (pintype "bidirectional"))
      (node (ref "LCD1") (pin "6") (pinfunction "E_6") (pintype "bidirectional"))
    )
    (net (code "119") (name "~{NMI}") (class "Default")
      (node (ref "CN1") (pin "P4") (pinfunction "NMI_P4") (pintype "passive"))
      (node (ref "IC3") (pin "77") (pinfunction "FB4MC7_77") (pintype "bidirectional"))
    )
    (net (code "120") (name "~{P2}") (class "Default")
      (node (ref "CN1") (pin "P36") (pinfunction "P2_P36") (pintype "passive"))
      (node (ref "IC3") (pin "89") (pinfunction "FB4MC15_89") (pintype "bidirectional"))
    )
    (net (code "121") (name "~{RAMCS}") (class "Default")
      (node (ref "IC2") (pin "20") (pinfunction "/CS1_20") (pintype "input"))
      (node (ref "IC3") (pin "3") (pinfunction "FB2MC7/GTS1_3") (pintype "bidirectional"))
    )
    (net (code "122") (name "~{RD}") (class "Default")
      (node (ref "IC1") (pin "24") (pinfunction "/OE_24") (pintype "input"))
      (node (ref "IC2") (pin "22") (pinfunction "/OE_22") (pintype "input"))
      (node (ref "IC3") (pin "9") (pinfunction "FB2MC14_9") (pintype "bidirectional"))
    )
    (net (code "123") (name "~{RESET_C}") (class "Default")
      (node (ref "D1") (pin "A") (pinfunction "A_A") (pintype "passive"))
      (node (ref "IC3") (pin "79") (pinfunction "FB4MC18_79") (pintype "bidirectional"))
      (node (ref "R3") (pin "1") (pinfunction "1_1") (pintype "passive"))
    )
    (net (code "124") (name "~{RESET}") (class "Default")
      (node (ref "CN1") (pin "P5") (pinfunction "RESET_P5") (pintype "passive"))
      (node (ref "D1") (pin "C") (pinfunction "C_C") (pintype "passive"))
    )
    (net (code "125") (name "~{ROMCS}") (class "Default")
      (node (ref "IC1") (pin "22") (pinfunction "/CS_22") (pintype "input"))
      (node (ref "IC3") (pin "25") (pinfunction "FB1MC7_25") (pintype "bidirectional"))
    )
    (net (code "126") (name "~{ROMWE}") (class "Default")
      (node (ref "IC1") (pin "31") (pinfunction "/WE_31") (pintype "input"))
      (node (ref "JP9") (pin "2") (pinfunction "2_2") (pintype "passive"))
    )
    (net (code "127") (name "~{WR}") (class "Default")
      (node (ref "IC2") (pin "27") (pinfunction "/WE_27") (pintype "input"))
      (node (ref "IC3") (pin "20") (pinfunction "FB1MC4_20") (pintype "bidirectional"))
      (node (ref "JP9") (pin "1") (pinfunction "1_1") (pintype "passive"))
    )
  )
)
